# uartto485.net
KiCad netlist of a schematic drawn in Altium Designer
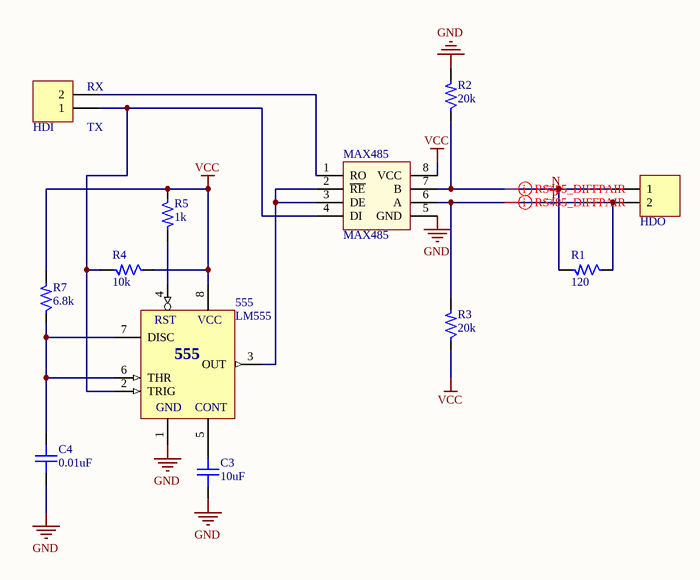
[diagram p0: uartto485.SchDoc]

(export (version "E")
  (design (tool "Eeschema 10.0.6"))
  (components
    (comp (ref "555")
      (value "LM555")
      (footprint "DIP8/W0.3")
      (description "Timer")
      (libsource (lib "echipkool-com-library") (part "LM555"))
    )
    (comp (ref "C3")
      (value "10uF")
      (footprint "CAPC-0603 (1608)")
      (description "CAP CER 33pF 50V 5%  0603")
      (fields (field (name "MPN") "CL10C330JB8NNNC, 0603N330J500CT"))
      (libsource (lib "BYTECH_HW_LIB_2019 (1)") (part "0603N330J500CT"))
    )
    (comp (ref "C4")
      (value "0.01uF")
      (footprint "CAPC-0603 (1608)")
      (description "CAP CER 33pF 50V 5%  0603")
      (fields (field (name "MPN") "CL10C330JB8NNNC, 0603N330J500CT"))
      (libsource (lib "BYTECH_HW_LIB_2019 (1)") (part "0603N330J500CT"))
    )
    (comp (ref "HDI")
      (value "Header 2_1")
      (footprint "HED2")
      (description "Header, 2-Pin")
      (fields (field (name "MANUFACTURER") "Generic Components"))
      (libsource (lib "") (part "Header 2_1_1"))
    )
    (comp (ref "HDO")
      (value "Header 2_1")
      (footprint "HED2")
      (description "Header, 2-Pin")
      (fields (field (name "MANUFACTURER") "Generic Components"))
      (libsource (lib "echipkool-com-library") (part "Header 2_1"))
    )
    (comp (ref "MAX485")
      (value "MAX485")
      (footprint "DIP8/W0.3")
      (description "RS232 - RS485 (Same sn75176)")
      (libsource (lib "echipkool-com-library") (part "MAX485"))
    )
    (comp (ref "R1")
      (value "120")
      (footprint "SM-RES-1206")
      (description "Resistor 1/4W")
      (libsource (lib "echipkool-com-library") (part "R"))
    )
    (comp (ref "R2")
      (value "20k")
      (footprint "SM-RES-1206")
      (description "Resistor 1/4W")
      (libsource (lib "echipkool-com-library") (part "R"))
    )
    (comp (ref "R3")
      (value "20k")
      (footprint "SM-RES-1206")
      (description "Resistor 1/4W")
      (libsource (lib "echipkool-com-library") (part "R"))
    )
    (comp (ref "R4")
      (value "10k")
      (footprint "SM-RES-1206")
      (description "Resistor 1/4W")
      (libsource (lib "echipkool-com-library") (part "R"))
    )
    (comp (ref "R5")
      (value "1k")
      (footprint "SM-RES-1206")
      (description "Resistor 1/4W")
      (libsource (lib "echipkool-com-library") (part "R"))
    )
    (comp (ref "R7")
      (value "6.8k")
      (footprint "SM-RES-1206")
      (description "Resistor 1/4W")
      (libsource (lib "echipkool-com-library") (part "R"))
    )
  )
  (nets
    (net (code "1") (name "/_N") (class "Default")
      (node (ref "HDO") (pin "1") (pinfunction "1_1") (pintype "passive"))
      (node (ref "MAX485") (pin "7") (pinfunction "B_7") (pintype "passive"))
      (node (ref "R1") (pin "2") (pinfunction "2_2") (pintype "passive"))
      (node (ref "R2") (pin "1") (pinfunction "1_1") (pintype "passive"))
    )
    (net (code "2") (name "/_P") (class "Default")
      (node (ref "HDO") (pin "2") (pinfunction "2_2") (pintype "passive"))
      (node (ref "MAX485") (pin "6") (pinfunction "A_6") (pintype "passive"))
      (node (ref "R1") (pin "1") (pinfunction "1_1") (pintype "passive"))
      (node (ref "R3") (pin "2") (pinfunction "2_2") (pintype "passive"))
    )
    (net (code "3") (name "GND") (class "Default")
      (node (ref "555") (pin "1") (pinfunction "GND_1") (pintype "power_in"))
      (node (ref "C3") (pin "1") (pinfunction "1_1") (pintype "passive"))
      (node (ref "C4") (pin "1") (pinfunction "1_1") (pintype "passive"))
      (node (ref "MAX485") (pin "5") (pinfunction "GND_5") (pintype "passive"))
      (node (ref "R2") (pin "2") (pinfunction "2_2") (pintype "passive"))
    )
    (net (code "4") (name "Net-(555-CONT)") (class "Default")
      (node (ref "555") (pin "5") (pinfunction "CONT_5") (pintype "passive"))
      (node (ref "C3") (pin "2") (pinfunction "2_2") (pintype "passive"))
    )
    (net (code "5") (name "Net-(555-DISC)") (class "Default")
      (node (ref "555") (pin "6") (pinfunction "THR_6") (pintype "input"))
      (node (ref "555") (pin "7") (pinfunction "DISC_7") (pintype "open_collector"))
      (node (ref "C4") (pin "2") (pinfunction "2_2") (pintype "passive"))
      (node (ref "R7") (pin "1") (pinfunction "1_1") (pintype "passive"))
    )
    (net (code "6") (name "Net-(555-OUT)") (class "Default")
      (node (ref "555") (pin "3") (pinfunction "OUT_3") (pintype "output"))
      (node (ref "MAX485") (pin "2") (pinfunction "~{RE}_2") (pintype "passive"))
      (node (ref "MAX485") (pin "3") (pinfunction "DE_3") (pintype "passive"))
    )
    (net (code "7") (name "Net-(555-RST)") (class "Default")
      (node (ref "555") (pin "4") (pinfunction "RST_4") (pintype "input"))
      (node (ref "R5") (pin "2") (pinfunction "2_2") (pintype "passive"))
    )
    (net (code "8") (name "Net-(555-TRIG)") (class "Default")
      (node (ref "555") (pin "2") (pinfunction "TRIG_2") (pintype "input"))
      (node (ref "HDI") (pin "1") (pinfunction "1_1") (pintype "passive"))
      (node (ref "MAX485") (pin "4") (pinfunction "DI_4") (pintype "passive"))
      (node (ref "R4") (pin "2") (pinfunction "2_2") (pintype "passive"))
    )
    (net (code "9") (name "Net-(MAX485-RO)") (class "Default")
      (node (ref "HDI") (pin "2") (pinfunction "2_2") (pintype "passive"))
      (node (ref "MAX485") (pin "1") (pinfunction "RO_1") (pintype "passive"))
    )
    (net (code "10") (name "VCC") (class "Default")
      (node (ref "555") (pin "8") (pinfunction "VCC_8") (pintype "power_in"))
      (node (ref "MAX485") (pin "8") (pinfunction "VCC_8") (pintype "passive"))
      (node (ref "R3") (pin "1") (pinfunction "1_1") (pintype "passive"))
      (node (ref "R4") (pin "1") (pinfunction "1_1") (pintype "passive"))
      (node (ref "R5") (pin "1") (pinfunction "1_1") (pintype "passive"))
      (node (ref "R7") (pin "2") (pinfunction "2_2") (pintype "passive"))
    )
  )
)
